# design.net
KiCad netlist of a schematic drawn in EasyEDA Pro
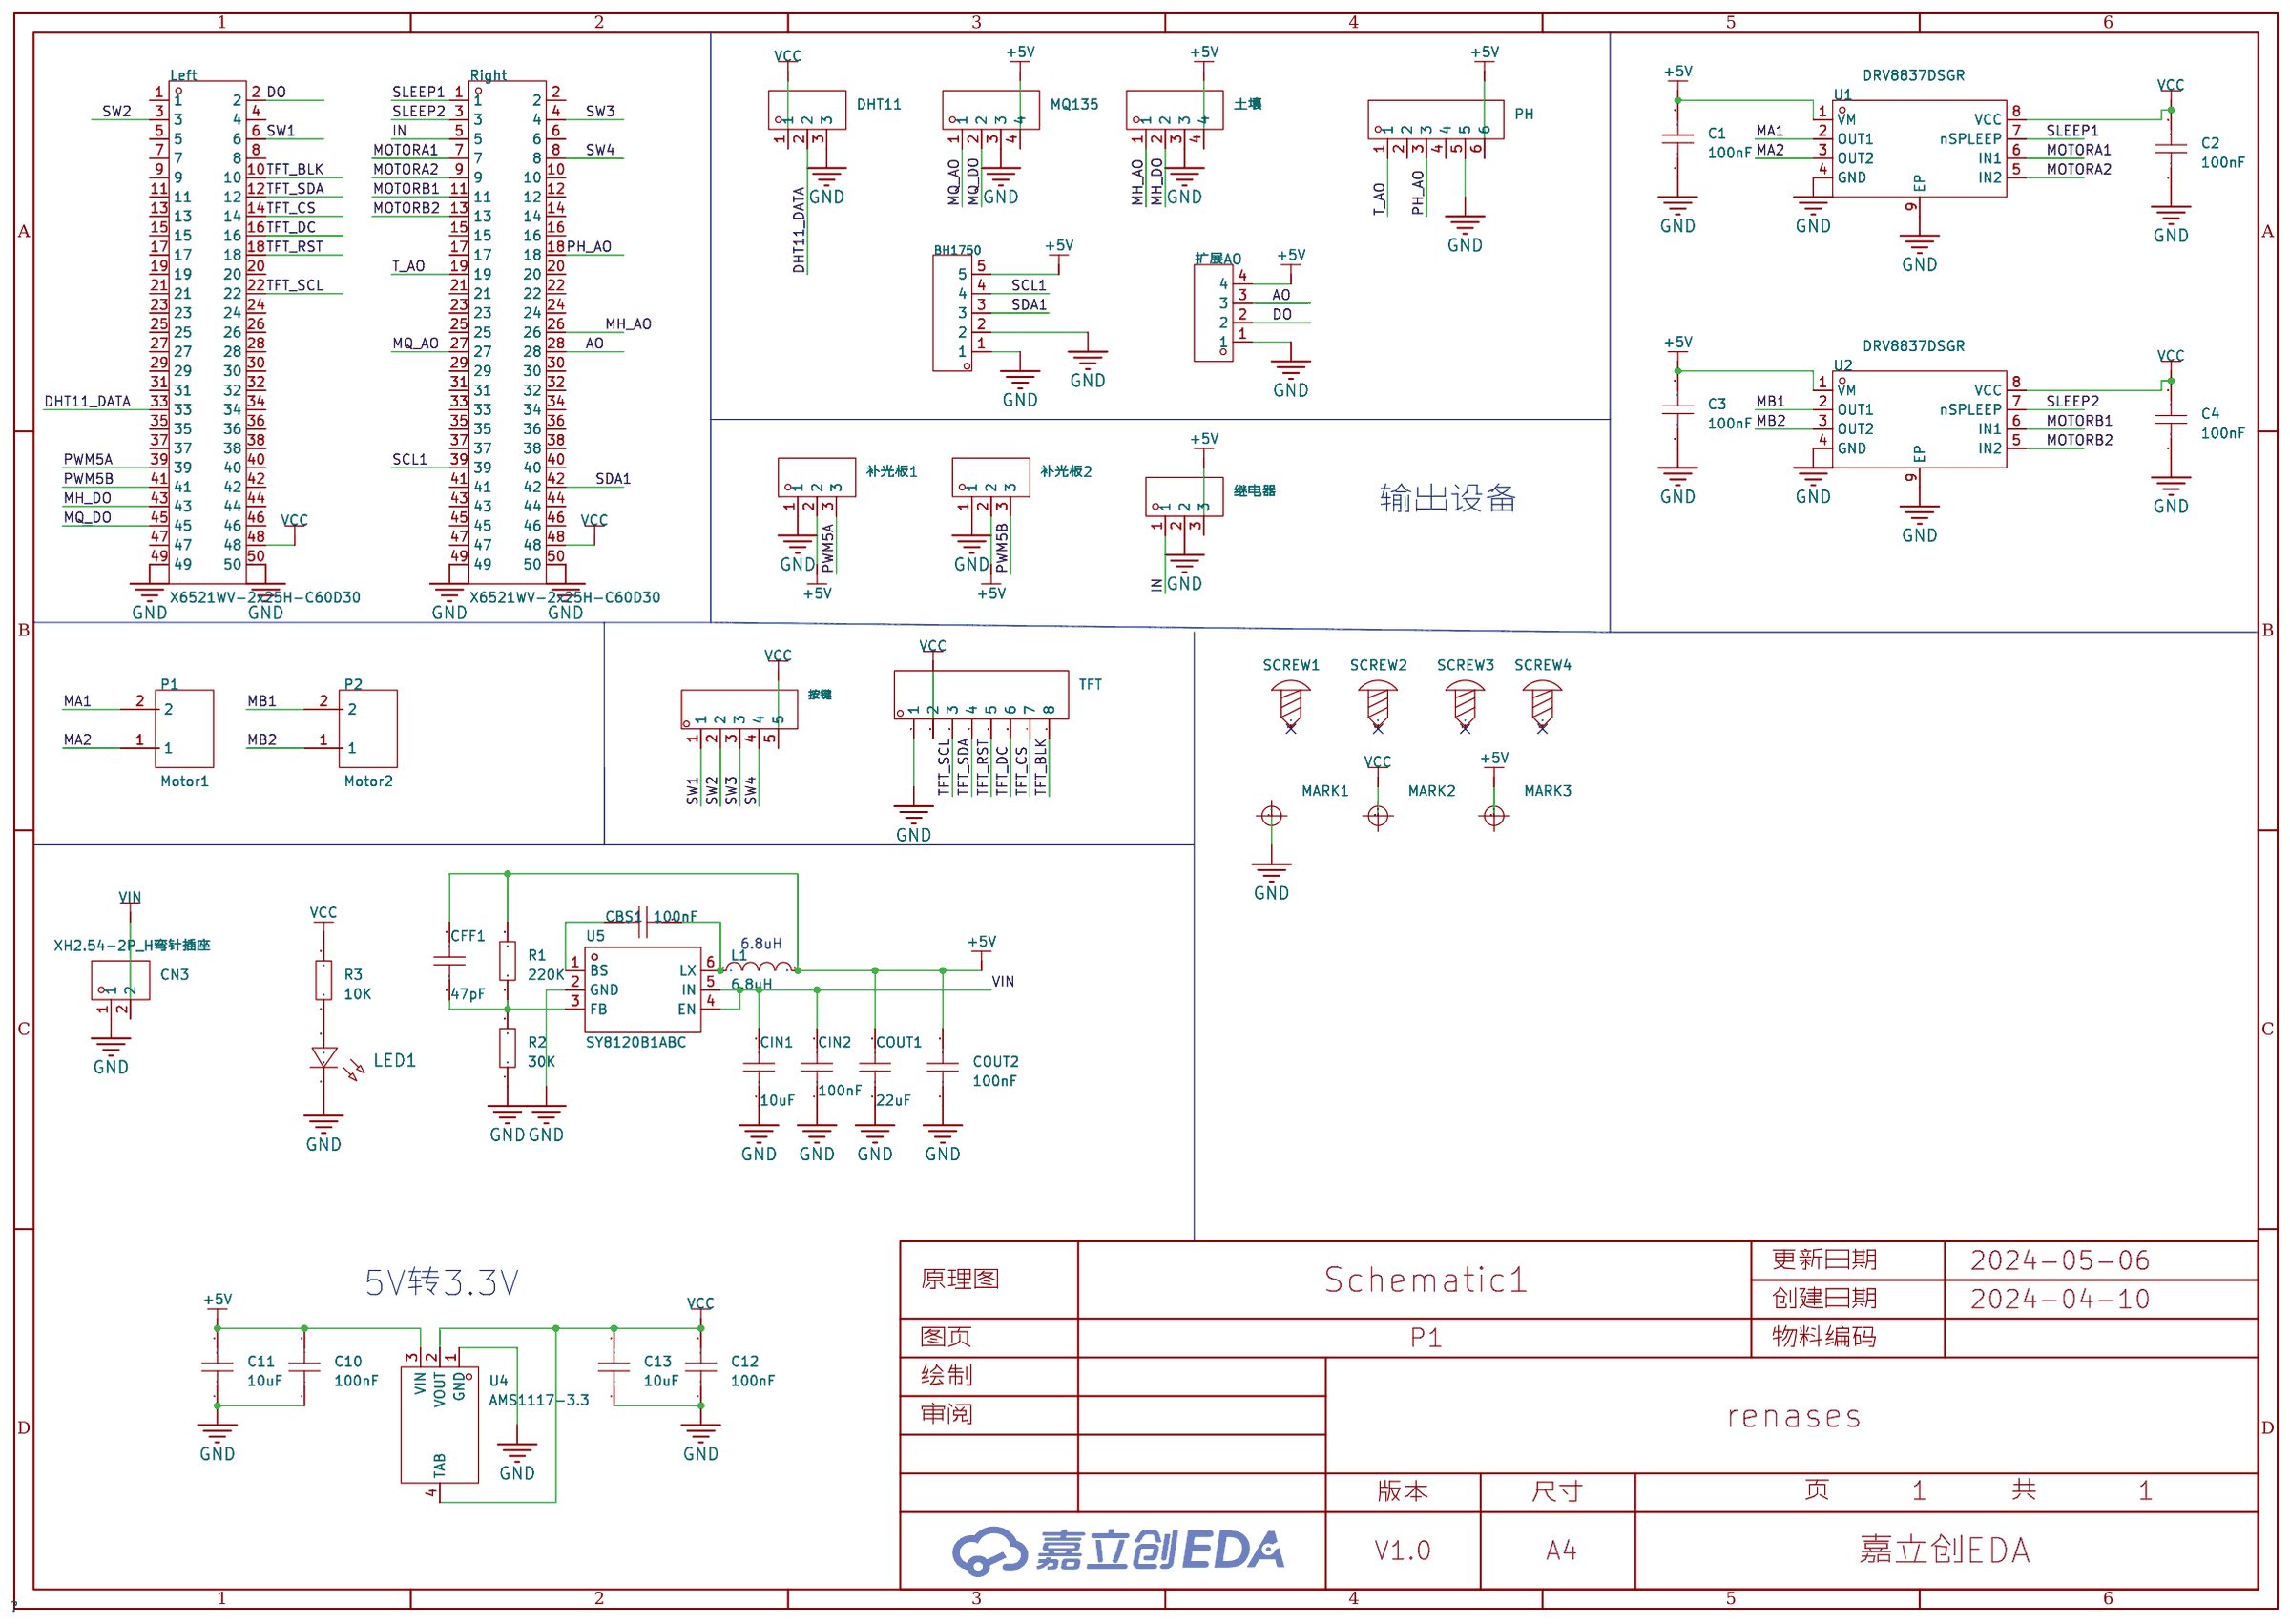
[diagram p0: schematic sheet]

(export (version "E")
  (design (tool "Eeschema 10.0.6"))
  (components
    (comp (ref "BH1750")
      (value "~")
      (footprint "easyedapro:HDR-TH_5P-P2.54-V-M")
      (libsource (lib "easyedapro") (part "MTP125-1105S1"))
    )
    (comp (ref "C1")
      (value "100nF")
      (footprint "easyedapro:C0603")
      (libsource (lib "easyedapro") (part "CapAcitance"))
    )
    (comp (ref "C2")
      (value "100nF")
      (footprint "easyedapro:C0603")
      (libsource (lib "easyedapro") (part "CapAcitance"))
    )
    (comp (ref "C3")
      (value "100nF")
      (footprint "easyedapro:C0603")
      (libsource (lib "easyedapro") (part "CapAcitance"))
    )
    (comp (ref "C4")
      (value "100nF")
      (footprint "easyedapro:C0603")
      (libsource (lib "easyedapro") (part "CapAcitance"))
    )
    (comp (ref "C10")
      (value "100nF")
      (footprint "easyedapro:C0603")
      (libsource (lib "easyedapro") (part "CapAcitance"))
    )
    (comp (ref "C11")
      (value "10uF")
      (footprint "easyedapro:C0603")
      (libsource (lib "easyedapro") (part "CapAcitance"))
    )
    (comp (ref "C12")
      (value "100nF")
      (footprint "easyedapro:C0603")
      (libsource (lib "easyedapro") (part "CapAcitance"))
    )
    (comp (ref "C13")
      (value "10uF")
      (footprint "easyedapro:C0603")
      (libsource (lib "easyedapro") (part "CapAcitance"))
    )
    (comp (ref "CBS1")
      (value "100nF")
      (footprint "easyedapro:C0603")
      (libsource (lib "easyedapro") (part "CapAcitance"))
    )
    (comp (ref "CFF1")
      (value "47pF")
      (footprint "easyedapro:C0603")
      (libsource (lib "easyedapro") (part "CapAcitance"))
    )
    (comp (ref "CIN1")
      (value "10uF")
      (footprint "easyedapro:C0603")
      (libsource (lib "easyedapro") (part "CapAcitance"))
    )
    (comp (ref "CIN2")
      (value "100nF")
      (footprint "easyedapro:C0603")
      (libsource (lib "easyedapro") (part "CapAcitance"))
    )
    (comp (ref "CN3")
      (value "XH2.54-2P_H弯针插座")
      (footprint "easyedapro:CONN-TH_2P-P2.5_XH2.54-2P_H")
      (libsource (lib "easyedapro") (part "XH2.54-2P_H弯针插座"))
    )
    (comp (ref "COUT1")
      (value "22uF")
      (footprint "easyedapro:C0603")
      (libsource (lib "easyedapro") (part "CapAcitance"))
    )
    (comp (ref "COUT2")
      (value "100nF")
      (footprint "easyedapro:C0603")
      (libsource (lib "easyedapro") (part "CapAcitance"))
    )
    (comp (ref "DHT11")
      (value "~")
      (footprint "easyedapro:HDR-TH_3P-P2.54-V-M")
      (libsource (lib "easyedapro") (part "PZ254V-11-03P_C2937625"))
    )
    (comp (ref "L1")
      (value "6.8uH")
      (footprint "easyedapro:IND-SMD_L7.0-W6.6")
      (description "电感值:6.8uH;精度:±20%;额定电流:5A;饱和电流(Isat):6A;类型:一体成型电感;")
      (fields (field (name "Manufacturer Part") "FXL0630-6R8-M") (field (name "Manufacturer") "cjiang(长江微电)"))
      (libsource (lib "easyedapro") (part "FXL0630-6R8-M"))
    )
    (comp (ref "LED1")
      (value "~")
      (footprint "easyedapro:LED_0603")
      (libsource (lib "easyedapro") (part "LED_R"))
    )
    (comp (ref "Left")
      (value "X6521WV-2x25H-C60D30")
      (footprint "easyedapro:HDR-TH_50P-2.54-V-M-R2-C25-S2.54")
      (fields (field (name "Manufacturer") "XKB Connection(中国星坤)"))
      (libsource (lib "easyedapro") (part "X6521WV-2×25H-C30D60"))
    )
    (comp (ref "MARK1")
      (value "~")
      (footprint "easyedapro:Mark-Point-1mm")
      (description "Mark点")
      (libsource (lib "easyedapro") (part "Mark-Point"))
    )
    (comp (ref "MARK2")
      (value "~")
      (footprint "easyedapro:Mark-Point-1mm")
      (description "Mark点")
      (libsource (lib "easyedapro") (part "Mark-Point"))
    )
    (comp (ref "MARK3")
      (value "~")
      (footprint "easyedapro:Mark-Point-1mm")
      (description "Mark点")
      (libsource (lib "easyedapro") (part "Mark-Point"))
    )
    (comp (ref "MQ135")
      (value "~")
      (footprint "easyedapro:HDR-TH_4P-P2.54-V-M")
      (libsource (lib "easyedapro") (part "PZ254V-11-04P"))
    )
    (comp (ref "P1")
      (value "Motor1")
      (footprint "easyedapro:CONN-TH_WJ126V-5.0-2P")
      (fields (field (name "Manufacturer") "KANGNEX(康奈克斯电气)"))
      (libsource (lib "easyedapro") (part "WJ126V-5.0-2P"))
    )
    (comp (ref "P2")
      (value "Motor2")
      (footprint "easyedapro:CONN-TH_WJ126V-5.0-2P")
      (fields (field (name "Manufacturer") "KANGNEX(康奈克斯电气)"))
      (libsource (lib "easyedapro") (part "WJ126V-5.0-2P"))
    )
    (comp (ref "PH")
      (value "~")
      (footprint "easyedapro:HDR-TH_6P-P2.54-V-F")
      (libsource (lib "easyedapro") (part "Header-Female-2.54_1x6"))
    )
    (comp (ref "R1")
      (value "220K")
      (footprint "easyedapro:Res_1/8W")
      (libsource (lib "easyedapro") (part "电阻"))
    )
    (comp (ref "R2")
      (value "30K")
      (footprint "easyedapro:Res_1/8W")
      (libsource (lib "easyedapro") (part "电阻"))
    )
    (comp (ref "R3")
      (value "10K")
      (footprint "easyedapro:Res_1/8W")
      (libsource (lib "easyedapro") (part "电阻"))
    )
    (comp (ref "Right")
      (value "X6521WV-2x25H-C60D30")
      (footprint "easyedapro:HDR-TH_50P-2.54-V-M-R2-C25-S2.54")
      (fields (field (name "Manufacturer") "XKB Connection(中国星坤)"))
      (libsource (lib "easyedapro") (part "X6521WV-2×25H-C30D60"))
    )
    (comp (ref "SCREW1")
      (value "~")
      (footprint "easyedapro:M3螺丝")
      (libsource (lib "easyedapro") (part "螺丝孔"))
    )
    (comp (ref "SCREW2")
      (value "~")
      (footprint "easyedapro:M3螺丝")
      (libsource (lib "easyedapro") (part "螺丝孔"))
    )
    (comp (ref "SCREW3")
      (value "~")
      (footprint "easyedapro:M3螺丝")
      (libsource (lib "easyedapro") (part "螺丝孔"))
    )
    (comp (ref "SCREW4")
      (value "~")
      (footprint "easyedapro:M3螺丝")
      (libsource (lib "easyedapro") (part "螺丝孔"))
    )
    (comp (ref "TFT")
      (value "~")
      (footprint "easyedapro:HDR-TH_8P-P2.54-V-M")
      (libsource (lib "easyedapro") (part "Header-Male-2.54_1x8"))
    )
    (comp (ref "U1")
      (value "DRV8837DSGR")
      (footprint "easyedapro:WSON-8_L2.0-W2.0-P0.50-TL-EP")
      (description "驱动电机类型:有刷直流电机;电源电压:1.8V~7V;输出电流:1.8A;接口:PWM;")
      (fields (field (name "Manufacturer") "TI(德州仪器)"))
      (libsource (lib "easyedapro") (part "DRV8837DSGR"))
    )
    (comp (ref "U2")
      (value "DRV8837DSGR")
      (footprint "easyedapro:WSON-8_L2.0-W2.0-P0.50-TL-EP")
      (description "驱动电机类型:有刷直流电机;电源电压:1.8V~7V;输出电流:1.8A;接口:PWM;")
      (fields (field (name "Manufacturer") "TI(德州仪器)"))
      (libsource (lib "easyedapro") (part "DRV8837DSGR"))
    )
    (comp (ref "U4")
      (value "AMS1117-3.3")
      (footprint "easyedapro:SOT-223-3_L6.5-W3.5-P3.05-LS7.0")
      (description "输出类型：固定 输出极性：正 最大输入电压：18V 输出电压：3.3V 输出电流：1A 电源纹波抑制比(PSRR)：60dB@(120Hz)。当前应用较多领域：三端稳压器，机顶盒")
      (fields (field (name "Manufacturer") "TWGMC(台湾迪嘉)"))
      (libsource (lib "easyedapro") (part "AMS1117-3.3_C5250992"))
    )
    (comp (ref "U5")
      (value "SY8120B1ABC")
      (footprint "easyedapro:SOT-23-6_L2.9-W1.6-P0.95-LS2.8-BL")
      (description "功能类型:降压型;输入电压:-;输出电流(最大值):-;")
      (fields (field (name "Manufacturer") "silergy(矽力杰)"))
      (libsource (lib "easyedapro") (part "SY8120B1ABC"))
    )
    (comp (ref "土壤")
      (value "~")
      (footprint "easyedapro:HDR-TH_4P-P2.54-V-M")
      (libsource (lib "easyedapro") (part "PZ254V-11-04P"))
    )
    (comp (ref "扩展AO")
      (value "~")
      (footprint "easyedapro:HDR-TH_4P-P2.54-V-M")
      (libsource (lib "easyedapro") (part "PZ254V-11-04P"))
    )
    (comp (ref "按键")
      (value "~")
      (footprint "easyedapro:HDR-TH_5P-P2.54-V-M")
      (libsource (lib "easyedapro") (part "MTP125-1105S1"))
    )
    (comp (ref "继电器")
      (value "~")
      (footprint "easyedapro:HDR-TH_3P-P2.54-V-M")
      (libsource (lib "easyedapro") (part "PZ254V-11-03P_C2937625"))
    )
    (comp (ref "补光板1")
      (value "~")
      (footprint "easyedapro:HDR-TH_3P-P2.54-V-M")
      (libsource (lib "easyedapro") (part "PZ254V-11-03P_C2937625"))
    )
    (comp (ref "补光板2")
      (value "~")
      (footprint "easyedapro:HDR-TH_3P-P2.54-V-M")
      (libsource (lib "easyedapro") (part "PZ254V-11-03P_C2937625"))
    )
  )
  (nets
    (net (code "1") (name "+5V") (class "Default")
      (node (ref "BH1750") (pin "5") (pinfunction "5_5") (pintype "input"))
      (node (ref "C1") (pin "2") (pinfunction "2_2") (pintype "input"))
      (node (ref "C10") (pin "2") (pinfunction "2_2") (pintype "input"))
      (node (ref "C11") (pin "2") (pinfunction "2_2") (pintype "input"))
      (node (ref "C3") (pin "2") (pinfunction "2_2") (pintype "input"))
      (node (ref "CFF1") (pin "2") (pinfunction "2_2") (pintype "input"))
      (node (ref "COUT1") (pin "2") (pinfunction "2_2") (pintype "input"))
      (node (ref "COUT2") (pin "2") (pinfunction "2_2") (pintype "input"))
      (node (ref "L1") (pin "2") (pinfunction "2_2") (pintype "unspecified"))
      (node (ref "MARK3") (pin "1") (pinfunction "1_1") (pintype "input"))
      (node (ref "MQ135") (pin "4") (pinfunction "4_4") (pintype "unspecified"))
      (node (ref "PH") (pin "6") (pinfunction "6_6") (pintype "unspecified"))
      (node (ref "R1") (pin "2") (pinfunction "2_2") (pintype "input"))
      (node (ref "U1") (pin "1") (pinfunction "VM_1") (pintype "unspecified"))
      (node (ref "U2") (pin "1") (pinfunction "VM_1") (pintype "unspecified"))
      (node (ref "U4") (pin "3") (pinfunction "VIN_3") (pintype "unspecified"))
      (node (ref "土壤") (pin "4") (pinfunction "4_4") (pintype "unspecified"))
      (node (ref "扩展AO") (pin "4") (pinfunction "4_4") (pintype "unspecified"))
      (node (ref "继电器") (pin "3") (pinfunction "3_3") (pintype "input"))
      (node (ref "补光板1") (pin "2") (pinfunction "2_2") (pintype "input"))
      (node (ref "补光板2") (pin "2") (pinfunction "2_2") (pintype "input"))
    )
    (net (code "2") (name "/AO") (class "Default")
      (node (ref "Right") (pin "28") (pinfunction "28_28") (pintype "unspecified"))
      (node (ref "扩展AO") (pin "3") (pinfunction "3_3") (pintype "unspecified"))
    )
    (net (code "3") (name "/DHT11_DATA") (class "Default")
      (node (ref "DHT11") (pin "2") (pinfunction "2_2") (pintype "input"))
      (node (ref "Left") (pin "33") (pinfunction "33_33") (pintype "unspecified"))
    )
    (net (code "4") (name "/DO") (class "Default")
      (node (ref "Left") (pin "2") (pinfunction "2_2") (pintype "unspecified"))
      (node (ref "扩展AO") (pin "2") (pinfunction "2_2") (pintype "unspecified"))
    )
    (net (code "5") (name "/IN") (class "Default")
      (node (ref "Right") (pin "5") (pinfunction "5_5") (pintype "unspecified"))
      (node (ref "继电器") (pin "1") (pinfunction "1_1") (pintype "input"))
    )
    (net (code "6") (name "/MA1") (class "Default")
      (node (ref "P1") (pin "2") (pinfunction "2_2") (pintype "input"))
      (node (ref "U1") (pin "2") (pinfunction "OUT1_2") (pintype "unspecified"))
    )
    (net (code "7") (name "/MA2") (class "Default")
      (node (ref "P1") (pin "1") (pinfunction "1_1") (pintype "input"))
      (node (ref "U1") (pin "3") (pinfunction "OUT2_3") (pintype "unspecified"))
    )
    (net (code "8") (name "/MB1") (class "Default")
      (node (ref "P2") (pin "2") (pinfunction "2_2") (pintype "input"))
      (node (ref "U2") (pin "2") (pinfunction "OUT1_2") (pintype "unspecified"))
    )
    (net (code "9") (name "/MB2") (class "Default")
      (node (ref "P2") (pin "1") (pinfunction "1_1") (pintype "input"))
      (node (ref "U2") (pin "3") (pinfunction "OUT2_3") (pintype "unspecified"))
    )
    (net (code "10") (name "/MH_AO") (class "Default")
      (node (ref "Right") (pin "26") (pinfunction "26_26") (pintype "unspecified"))
      (node (ref "土壤") (pin "1") (pinfunction "1_1") (pintype "unspecified"))
    )
    (net (code "11") (name "/MH_DO") (class "Default")
      (node (ref "Left") (pin "43") (pinfunction "43_43") (pintype "unspecified"))
      (node (ref "土壤") (pin "2") (pinfunction "2_2") (pintype "unspecified"))
    )
    (net (code "12") (name "/MOTORA1") (class "Default")
      (node (ref "Right") (pin "7") (pinfunction "7_7") (pintype "unspecified"))
      (node (ref "U1") (pin "6") (pinfunction "IN1_6") (pintype "unspecified"))
    )
    (net (code "13") (name "/MOTORA2") (class "Default")
      (node (ref "Right") (pin "9") (pinfunction "9_9") (pintype "unspecified"))
      (node (ref "U1") (pin "5") (pinfunction "IN2_5") (pintype "unspecified"))
    )
    (net (code "14") (name "/MOTORB1") (class "Default")
      (node (ref "Right") (pin "11") (pinfunction "11_11") (pintype "unspecified"))
      (node (ref "U2") (pin "6") (pinfunction "IN1_6") (pintype "unspecified"))
    )
    (net (code "15") (name "/MOTORB2") (class "Default")
      (node (ref "Right") (pin "13") (pinfunction "13_13") (pintype "unspecified"))
      (node (ref "U2") (pin "5") (pinfunction "IN2_5") (pintype "unspecified"))
    )
    (net (code "16") (name "/MQ_AO") (class "Default")
      (node (ref "MQ135") (pin "1") (pinfunction "1_1") (pintype "unspecified"))
      (node (ref "Right") (pin "27") (pinfunction "27_27") (pintype "unspecified"))
    )
    (net (code "17") (name "/MQ_DO") (class "Default")
      (node (ref "Left") (pin "45") (pinfunction "45_45") (pintype "unspecified"))
      (node (ref "MQ135") (pin "2") (pinfunction "2_2") (pintype "unspecified"))
    )
    (net (code "18") (name "/PH_AO") (class "Default")
      (node (ref "PH") (pin "3") (pinfunction "3_3") (pintype "unspecified"))
      (node (ref "Right") (pin "18") (pinfunction "18_18") (pintype "unspecified"))
    )
    (net (code "19") (name "/PWM5A") (class "Default")
      (node (ref "Left") (pin "39") (pinfunction "39_39") (pintype "unspecified"))
      (node (ref "补光板1") (pin "3") (pinfunction "3_3") (pintype "input"))
    )
    (net (code "20") (name "/PWM5B") (class "Default")
      (node (ref "Left") (pin "41") (pinfunction "41_41") (pintype "unspecified"))
      (node (ref "补光板2") (pin "3") (pinfunction "3_3") (pintype "input"))
    )
    (net (code "21") (name "/SCL1") (class "Default")
      (node (ref "BH1750") (pin "4") (pinfunction "4_4") (pintype "input"))
      (node (ref "Right") (pin "39") (pinfunction "39_39") (pintype "unspecified"))
    )
    (net (code "22") (name "/SDA1") (class "Default")
      (node (ref "BH1750") (pin "3") (pinfunction "3_3") (pintype "input"))
      (node (ref "Right") (pin "42") (pinfunction "42_42") (pintype "unspecified"))
    )
    (net (code "23") (name "/SLEEP1") (class "Default")
      (node (ref "Right") (pin "1") (pinfunction "1_1") (pintype "unspecified"))
      (node (ref "U1") (pin "7") (pinfunction "nSPLEEP_7") (pintype "unspecified"))
    )
    (net (code "24") (name "/SLEEP2") (class "Default")
      (node (ref "Right") (pin "3") (pinfunction "3_3") (pintype "unspecified"))
      (node (ref "U2") (pin "7") (pinfunction "nSPLEEP_7") (pintype "unspecified"))
    )
    (net (code "25") (name "/SW1") (class "Default")
      (node (ref "Left") (pin "6") (pinfunction "6_6") (pintype "unspecified"))
      (node (ref "按键") (pin "1") (pinfunction "1_1") (pintype "input"))
    )
    (net (code "26") (name "/SW2") (class "Default")
      (node (ref "Left") (pin "3") (pinfunction "3_3") (pintype "unspecified"))
      (node (ref "按键") (pin "2") (pinfunction "2_2") (pintype "input"))
    )
    (net (code "27") (name "/SW3") (class "Default")
      (node (ref "Right") (pin "4") (pinfunction "4_4") (pintype "unspecified"))
      (node (ref "按键") (pin "3") (pinfunction "3_3") (pintype "input"))
    )
    (net (code "28") (name "/SW4") (class "Default")
      (node (ref "Right") (pin "8") (pinfunction "8_8") (pintype "unspecified"))
      (node (ref "按键") (pin "4") (pinfunction "4_4") (pintype "input"))
    )
    (net (code "29") (name "/TFT_BLK") (class "Default")
      (node (ref "Left") (pin "10") (pinfunction "10_10") (pintype "unspecified"))
      (node (ref "TFT") (pin "8") (pinfunction "8_8") (pintype "unspecified"))
    )
    (net (code "30") (name "/TFT_CS") (class "Default")
      (node (ref "Left") (pin "14") (pinfunction "14_14") (pintype "unspecified"))
      (node (ref "TFT") (pin "7") (pinfunction "7_7") (pintype "unspecified"))
    )
    (net (code "31") (name "/TFT_DC") (class "Default")
      (node (ref "Left") (pin "16") (pinfunction "16_16") (pintype "unspecified"))
      (node (ref "TFT") (pin "6") (pinfunction "6_6") (pintype "unspecified"))
    )
    (net (code "32") (name "/TFT_RST") (class "Default")
      (node (ref "Left") (pin "18") (pinfunction "18_18") (pintype "unspecified"))
      (node (ref "TFT") (pin "5") (pinfunction "5_5") (pintype "unspecified"))
    )
    (net (code "33") (name "/TFT_SCL") (class "Default")
      (node (ref "Left") (pin "22") (pinfunction "22_22") (pintype "unspecified"))
      (node (ref "TFT") (pin "3") (pinfunction "3_3") (pintype "unspecified"))
    )
    (net (code "34") (name "/TFT_SDA") (class "Default")
      (node (ref "Left") (pin "12") (pinfunction "12_12") (pintype "unspecified"))
      (node (ref "TFT") (pin "4") (pinfunction "4_4") (pintype "unspecified"))
    )
    (net (code "35") (name "/T_AO") (class "Default")
      (node (ref "PH") (pin "1") (pinfunction "1_1") (pintype "unspecified"))
      (node (ref "Right") (pin "19") (pinfunction "19_19") (pintype "unspecified"))
    )
    (net (code "36") (name "GND") (class "Default")
      (node (ref "BH1750") (pin "1") (pinfunction "1_1") (pintype "input"))
      (node (ref "BH1750") (pin "2") (pinfunction "2_2") (pintype "input"))
      (node (ref "C1") (pin "1") (pinfunction "1_1") (pintype "input"))
      (node (ref "C10") (pin "1") (pinfunction "1_1") (pintype "input"))
      (node (ref "C11") (pin "1") (pinfunction "1_1") (pintype "input"))
      (node (ref "C12") (pin "1") (pinfunction "1_1") (pintype "input"))
      (node (ref "C13") (pin "1") (pinfunction "1_1") (pintype "input"))
      (node (ref "C2") (pin "1") (pinfunction "1_1") (pintype "input"))
      (node (ref "C3") (pin "1") (pinfunction "1_1") (pintype "input"))
      (node (ref "C4") (pin "1") (pinfunction "1_1") (pintype "input"))
      (node (ref "CIN1") (pin "1") (pinfunction "1_1") (pintype "input"))
      (node (ref "CIN2") (pin "1") (pinfunction "1_1") (pintype "input"))
      (node (ref "CN3") (pin "1") (pinfunction "1_1") (pintype "input"))
      (node (ref "COUT1") (pin "1") (pinfunction "1_1") (pintype "input"))
      (node (ref "COUT2") (pin "1") (pinfunction "1_1") (pintype "input"))
      (node (ref "DHT11") (pin "3") (pinfunction "3_3") (pintype "input"))
      (node (ref "LED1") (pin "1") (pinfunction "C_1") (pintype "input"))
      (node (ref "Left") (pin "49") (pinfunction "49_49") (pintype "unspecified"))
      (node (ref "Left") (pin "50") (pinfunction "50_50") (pintype "unspecified"))
      (node (ref "MARK1") (pin "1") (pinfunction "1_1") (pintype "input"))
      (node (ref "MQ135") (pin "3") (pinfunction "3_3") (pintype "unspecified"))
      (node (ref "PH") (pin "5") (pinfunction "5_5") (pintype "unspecified"))
      (node (ref "R2") (pin "1") (pinfunction "1_1") (pintype "input"))
      (node (ref "Right") (pin "49") (pinfunction "49_49") (pintype "unspecified"))
      (node (ref "Right") (pin "50") (pinfunction "50_50") (pintype "unspecified"))
      (node (ref "TFT") (pin "1") (pinfunction "1_1") (pintype "unspecified"))
      (node (ref "U1") (pin "4") (pinfunction "GND_4") (pintype "unspecified"))
      (node (ref "U1") (pin "9") (pinfunction "EP_9") (pintype "unspecified"))
      (node (ref "U2") (pin "4") (pinfunction "GND_4") (pintype "unspecified"))
      (node (ref "U2") (pin "9") (pinfunction "EP_9") (pintype "unspecified"))
      (node (ref "U4") (pin "1") (pinfunction "GND_1") (pintype "unspecified"))
      (node (ref "U5") (pin "2") (pinfunction "GND_2") (pintype "unspecified"))
      (node (ref "土壤") (pin "3") (pinfunction "3_3") (pintype "unspecified"))
      (node (ref "扩展AO") (pin "1") (pinfunction "1_1") (pintype "unspecified"))
      (node (ref "继电器") (pin "2") (pinfunction "2_2") (pintype "input"))
      (node (ref "补光板1") (pin "1") (pinfunction "1_1") (pintype "input"))
      (node (ref "补光板2") (pin "1") (pinfunction "1_1") (pintype "input"))
    )
    (net (code "37") (name "Net-(LED1-A)") (class "Default")
      (node (ref "LED1") (pin "2") (pinfunction "A_2") (pintype "input"))
      (node (ref "R3") (pin "1") (pinfunction "1_1") (pintype "input"))
    )
    (net (code "38") (name "Net-(U5-BS)") (class "Default")
      (node (ref "CBS1") (pin "1") (pinfunction "1_1") (pintype "input"))
      (node (ref "U5") (pin "1") (pinfunction "BS_1") (pintype "unspecified"))
    )
    (net (code "39") (name "Net-(U5-FB)") (class "Default")
      (node (ref "CFF1") (pin "1") (pinfunction "1_1") (pintype "input"))
      (node (ref "R1") (pin "1") (pinfunction "1_1") (pintype "input"))
      (node (ref "R2") (pin "2") (pinfunction "2_2") (pintype "input"))
      (node (ref "U5") (pin "3") (pinfunction "FB_3") (pintype "unspecified"))
    )
    (net (code "40") (name "Net-(U5-LX)") (class "Default")
      (node (ref "CBS1") (pin "2") (pinfunction "2_2") (pintype "input"))
      (node (ref "L1") (pin "1") (pinfunction "1_1") (pintype "unspecified"))
      (node (ref "U5") (pin "6") (pinfunction "LX_6") (pintype "unspecified"))
    )
    (net (code "41") (name "VCC") (class "Default")
      (node (ref "C12") (pin "2") (pinfunction "2_2") (pintype "input"))
      (node (ref "C13") (pin "2") (pinfunction "2_2") (pintype "input"))
      (node (ref "C2") (pin "2") (pinfunction "2_2") (pintype "input"))
      (node (ref "C4") (pin "2") (pinfunction "2_2") (pintype "input"))
      (node (ref "DHT11") (pin "1") (pinfunction "1_1") (pintype "input"))
      (node (ref "Left") (pin "48") (pinfunction "48_48") (pintype "unspecified"))
      (node (ref "MARK2") (pin "1") (pinfunction "1_1") (pintype "input"))
      (node (ref "R3") (pin "2") (pinfunction "2_2") (pintype "input"))
      (node (ref "Right") (pin "48") (pinfunction "48_48") (pintype "unspecified"))
      (node (ref "TFT") (pin "2") (pinfunction "2_2") (pintype "unspecified"))
      (node (ref "U1") (pin "8") (pinfunction "VCC_8") (pintype "unspecified"))
      (node (ref "U2") (pin "8") (pinfunction "VCC_8") (pintype "unspecified"))
      (node (ref "U4") (pin "2") (pinfunction "VOUT_2") (pintype "unspecified"))
      (node (ref "U4") (pin "4") (pinfunction "TAB_4") (pintype "unspecified"))
      (node (ref "按键") (pin "5") (pinfunction "5_5") (pintype "input"))
    )
    (net (code "42") (name "VIN") (class "Default")
      (node (ref "CIN1") (pin "2") (pinfunction "2_2") (pintype "input"))
      (node (ref "CIN2") (pin "2") (pinfunction "2_2") (pintype "input"))
      (node (ref "CN3") (pin "2") (pinfunction "2_2") (pintype "input"))
      (node (ref "U5") (pin "4") (pinfunction "EN_4") (pintype "unspecified"))
      (node (ref "U5") (pin "5") (pinfunction "IN_5") (pintype "unspecified"))
    )
    (net (code "43") (name "unconnected-(Left-Pad1)") (class "Default")
      (node (ref "Left") (pin "1") (pinfunction "1_1") (pintype "unspecified"))
    )
    (net (code "44") (name "unconnected-(Left-Pad4)") (class "Default")
      (node (ref "Left") (pin "4") (pinfunction "4_4") (pintype "unspecified"))
    )
    (net (code "45") (name "unconnected-(Left-Pad5)") (class "Default")
      (node (ref "Left") (pin "5") (pinfunction "5_5") (pintype "unspecified"))
    )
    (net (code "46") (name "unconnected-(Left-Pad7)") (class "Default")
      (node (ref "Left") (pin "7") (pinfunction "7_7") (pintype "unspecified"))
    )
    (net (code "47") (name "unconnected-(Left-Pad8)") (class "Default")
      (node (ref "Left") (pin "8") (pinfunction "8_8") (pintype "unspecified"))
    )
    (net (code "48") (name "unconnected-(Left-Pad9)") (class "Default")
      (node (ref "Left") (pin "9") (pinfunction "9_9") (pintype "unspecified"))
    )
    (net (code "49") (name "unconnected-(Left-Pad11)") (class "Default")
      (node (ref "Left") (pin "11") (pinfunction "11_11") (pintype "unspecified"))
    )
    (net (code "50") (name "unconnected-(Left-Pad13)") (class "Default")
      (node (ref "Left") (pin "13") (pinfunction "13_13") (pintype "unspecified"))
    )
    (net (code "51") (name "unconnected-(Left-Pad15)") (class "Default")
      (node (ref "Left") (pin "15") (pinfunction "15_15") (pintype "unspecified"))
    )
    (net (code "52") (name "unconnected-(Left-Pad17)") (class "Default")
      (node (ref "Left") (pin "17") (pinfunction "17_17") (pintype "unspecified"))
    )
    (net (code "53") (name "unconnected-(Left-Pad19)") (class "Default")
      (node (ref "Left") (pin "19") (pinfunction "19_19") (pintype "unspecified"))
    )
    (net (code "54") (name "unconnected-(Left-Pad20)") (class "Default")
      (node (ref "Left") (pin "20") (pinfunction "20_20") (pintype "unspecified"))
    )
    (net (code "55") (name "unconnected-(Left-Pad21)") (class "Default")
      (node (ref "Left") (pin "21") (pinfunction "21_21") (pintype "unspecified"))
    )
    (net (code "56") (name "unconnected-(Left-Pad23)") (class "Default")
      (node (ref "Left") (pin "23") (pinfunction "23_23") (pintype "unspecified"))
    )
    (net (code "57") (name "unconnected-(Left-Pad24)") (class "Default")
      (node (ref "Left") (pin "24") (pinfunction "24_24") (pintype "unspecified"))
    )
    (net (code "58") (name "unconnected-(Left-Pad25)") (class "Default")
      (node (ref "Left") (pin "25") (pinfunction "25_25") (pintype "unspecified"))
    )
    (net (code "59") (name "unconnected-(Left-Pad26)") (class "Default")
      (node (ref "Left") (pin "26") (pinfunction "26_26") (pintype "unspecified"))
    )
    (net (code "60") (name "unconnected-(Left-Pad27)") (class "Default")
      (node (ref "Left") (pin "27") (pinfunction "27_27") (pintype "unspecified"))
    )
    (net (code "61") (name "unconnected-(Left-Pad28)") (class "Default")
      (node (ref "Left") (pin "28") (pinfunction "28_28") (pintype "unspecified"))
    )
    (net (code "62") (name "unconnected-(Left-Pad29)") (class "Default")
      (node (ref "Left") (pin "29") (pinfunction "29_29") (pintype "unspecified"))
    )
    (net (code "63") (name "unconnected-(Left-Pad30)") (class "Default")
      (node (ref "Left") (pin "30") (pinfunction "30_30") (pintype "unspecified"))
    )
    (net (code "64") (name "unconnected-(Left-Pad31)") (class "Default")
      (node (ref "Left") (pin "31") (pinfunction "31_31") (pintype "unspecified"))
    )
    (net (code "65") (name "unconnected-(Left-Pad32)") (class "Default")
      (node (ref "Left") (pin "32") (pinfunction "32_32") (pintype "unspecified"))
    )
    (net (code "66") (name "unconnected-(Left-Pad34)") (class "Default")
      (node (ref "Left") (pin "34") (pinfunction "34_34") (pintype "unspecified"))
    )
    (net (code "67") (name "unconnected-(Left-Pad35)") (class "Default")
      (node (ref "Left") (pin "35") (pinfunction "35_35") (pintype "unspecified"))
    )
    (net (code "68") (name "unconnected-(Left-Pad36)") (class "Default")
      (node (ref "Left") (pin "36") (pinfunction "36_36") (pintype "unspecified"))
    )
    (net (code "69") (name "unconnected-(Left-Pad37)") (class "Default")
      (node (ref "Left") (pin "37") (pinfunction "37_37") (pintype "unspecified"))
    )
    (net (code "70") (name "unconnected-(Left-Pad38)") (class "Default")
      (node (ref "Left") (pin "38") (pinfunction "38_38") (pintype "unspecified"))
    )
    (net (code "71") (name "unconnected-(Left-Pad40)") (class "Default")
      (node (ref "Left") (pin "40") (pinfunction "40_40") (pintype "unspecified"))
    )
    (net (code "72") (name "unconnected-(Left-Pad42)") (class "Default")
      (node (ref "Left") (pin "42") (pinfunction "42_42") (pintype "unspecified"))
    )
    (net (code "73") (name "unconnected-(Left-Pad44)") (class "Default")
      (node (ref "Left") (pin "44") (pinfunction "44_44") (pintype "unspecified"))
    )
    (net (code "74") (name "unconnected-(Left-Pad46)") (class "Default")
      (node (ref "Left") (pin "46") (pinfunction "46_46") (pintype "unspecified"))
    )
    (net (code "75") (name "unconnected-(Left-Pad47)") (class "Default")
      (node (ref "Left") (pin "47") (pinfunction "47_47") (pintype "unspecified"))
    )
    (net (code "76") (name "unconnected-(PH-Pad2)") (class "Default")
      (node (ref "PH") (pin "2") (pinfunction "2_2") (pintype "unspecified"))
    )
    (net (code "77") (name "unconnected-(PH-Pad4)") (class "Default")
      (node (ref "PH") (pin "4") (pinfunction "4_4") (pintype "unspecified"))
    )
    (net (code "78") (name "unconnected-(Right-Pad2)") (class "Default")
      (node (ref "Right") (pin "2") (pinfunction "2_2") (pintype "unspecified"))
    )
    (net (code "79") (name "unconnected-(Right-Pad6)") (class "Default")
      (node (ref "Right") (pin "6") (pinfunction "6_6") (pintype "unspecified"))
    )
    (net (code "80") (name "unconnected-(Right-Pad10)") (class "Default")
      (node (ref "Right") (pin "10") (pinfunction "10_10") (pintype "unspecified"))
    )
    (net (code "81") (name "unconnected-(Right-Pad12)") (class "Default")
      (node (ref "Right") (pin "12") (pinfunction "12_12") (pintype "unspecified"))
    )
    (net (code "82") (name "unconnected-(Right-Pad14)") (class "Default")
      (node (ref "Right") (pin "14") (pinfunction "14_14") (pintype "unspecified"))
    )
    (net (code "83") (name "unconnected-(Right-Pad15)") (class "Default")
      (node (ref "Right") (pin "15") (pinfunction "15_15") (pintype "unspecified"))
    )
    (net (code "84") (name "unconnected-(Right-Pad16)") (class "Default")
      (node (ref "Right") (pin "16") (pinfunction "16_16") (pintype "unspecified"))
    )
    (net (code "85") (name "unconnected-(Right-Pad17)") (class "Default")
      (node (ref "Right") (pin "17") (pinfunction "17_17") (pintype "unspecified"))
    )
    (net (code "86") (name "unconnected-(Right-Pad20)") (class "Default")
      (node (ref "Right") (pin "20") (pinfunction "20_20") (pintype "unspecified"))
    )
    (net (code "87") (name "unconnected-(Right-Pad21)") (class "Default")
      (node (ref "Right") (pin "21") (pinfunction "21_21") (pintype "unspecified"))
    )
    (net (code "88") (name "unconnected-(Right-Pad22)") (class "Default")
      (node (ref "Right") (pin "22") (pinfunction "22_22") (pintype "unspecified"))
    )
    (net (code "89") (name "unconnected-(Right-Pad23)") (class "Default")
      (node (ref "Right") (pin "23") (pinfunction "23_23") (pintype "unspecified"))
    )
    (net (code "90") (name "unconnected-(Right-Pad24)") (class "Default")
      (node (ref "Right") (pin "24") (pinfunction "24_24") (pintype "unspecified"))
    )
    (net (code "91") (name "unconnected-(Right-Pad25)") (class "Default")
      (node (ref "Right") (pin "25") (pinfunction "25_25") (pintype "unspecified"))
    )
    (net (code "92") (name "unconnected-(Right-Pad29)") (class "Default")
      (node (ref "Right") (pin "29") (pinfunction "29_29") (pintype "unspecified"))
    )
    (net (code "93") (name "unconnected-(Right-Pad30)") (class "Default")
      (node (ref "Right") (pin "30") (pinfunction "30_30") (pintype "unspecified"))
    )
    (net (code "94") (name "unconnected-(Right-Pad31)") (class "Default")
      (node (ref "Right") (pin "31") (pinfunction "31_31") (pintype "unspecified"))
    )
    (net (code "95") (name "unconnected-(Right-Pad32)") (class "Default")
      (node (ref "Right") (pin "32") (pinfunction "32_32") (pintype "unspecified"))
    )
    (net (code "96") (name "unconnected-(Right-Pad33)") (class "Default")
      (node (ref "Right") (pin "33") (pinfunction "33_33") (pintype "unspecified"))
    )
    (net (code "97") (name "unconnected-(Right-Pad34)") (class "Default")
      (node (ref "Right") (pin "34") (pinfunction "34_34") (pintype "unspecified"))
    )
    (net (code "98") (name "unconnected-(Right-Pad35)") (class "Default")
      (node (ref "Right") (pin "35") (pinfunction "35_35") (pintype "unspecified"))
    )
    (net (code "99") (name "unconnected-(Right-Pad36)") (class "Default")
      (node (ref "Right") (pin "36") (pinfunction "36_36") (pintype "unspecified"))
    )
    (net (code "100") (name "unconnected-(Right-Pad37)") (class "Default")
      (node (ref "Right") (pin "37") (pinfunction "37_37") (pintype "unspecified"))
    )
    (net (code "101") (name "unconnected-(Right-Pad38)") (class "Default")
      (node (ref "Right") (pin "38") (pinfunction "38_38") (pintype "unspecified"))
    )
    (net (code "102") (name "unconnected-(Right-Pad40)") (class "Default")
      (node (ref "Right") (pin "40") (pinfunction "40_40") (pintype "unspecified"))
    )
    (net (code "103") (name "unconnected-(Right-Pad41)") (class "Default")
      (node (ref "Right") (pin "41") (pinfunction "41_41") (pintype "unspecified"))
    )
    (net (code "104") (name "unconnected-(Right-Pad43)") (class "Default")
      (node (ref "Right") (pin "43") (pinfunction "43_43") (pintype "unspecified"))
    )
    (net (code "105") (name "unconnected-(Right-Pad44)") (class "Default")
      (node (ref "Right") (pin "44") (pinfunction "44_44") (pintype "unspecified"))
    )
    (net (code "106") (name "unconnected-(Right-Pad45)") (class "Default")
      (node (ref "Right") (pin "45") (pinfunction "45_45") (pintype "unspecified"))
    )
    (net (code "107") (name "unconnected-(Right-Pad46)") (class "Default")
      (node (ref "Right") (pin "46") (pinfunction "46_46") (pintype "unspecified"))
    )
    (net (code "108") (name "unconnected-(Right-Pad47)") (class "Default")
      (node (ref "Right") (pin "47") (pinfunction "47_47") (pintype "unspecified"))
    )
    (net (code "109") (name "unconnected-(SCREW1-Pad1)") (class "Default")
      (node (ref "SCREW1") (pin "1") (pinfunction "1_1") (pintype "input+no_connect"))
    )
    (net (code "110") (name "unconnected-(SCREW2-Pad1)") (class "Default")
      (node (ref "SCREW2") (pin "1") (pinfunction "1_1") (pintype "input+no_connect"))
    )
    (net (code "111") (name "unconnected-(SCREW3-Pad1)") (class "Default")
      (node (ref "SCREW3") (pin "1") (pinfunction "1_1") (pintype "input+no_connect"))
    )
    (net (code "112") (name "unconnected-(SCREW4-Pad1)") (class "Default")
      (node (ref "SCREW4") (pin "1") (pinfunction "1_1") (pintype "input+no_connect"))
    )
  )
)
